# Main_Power.net
KiCad netlist of a schematic drawn in Altium Designer
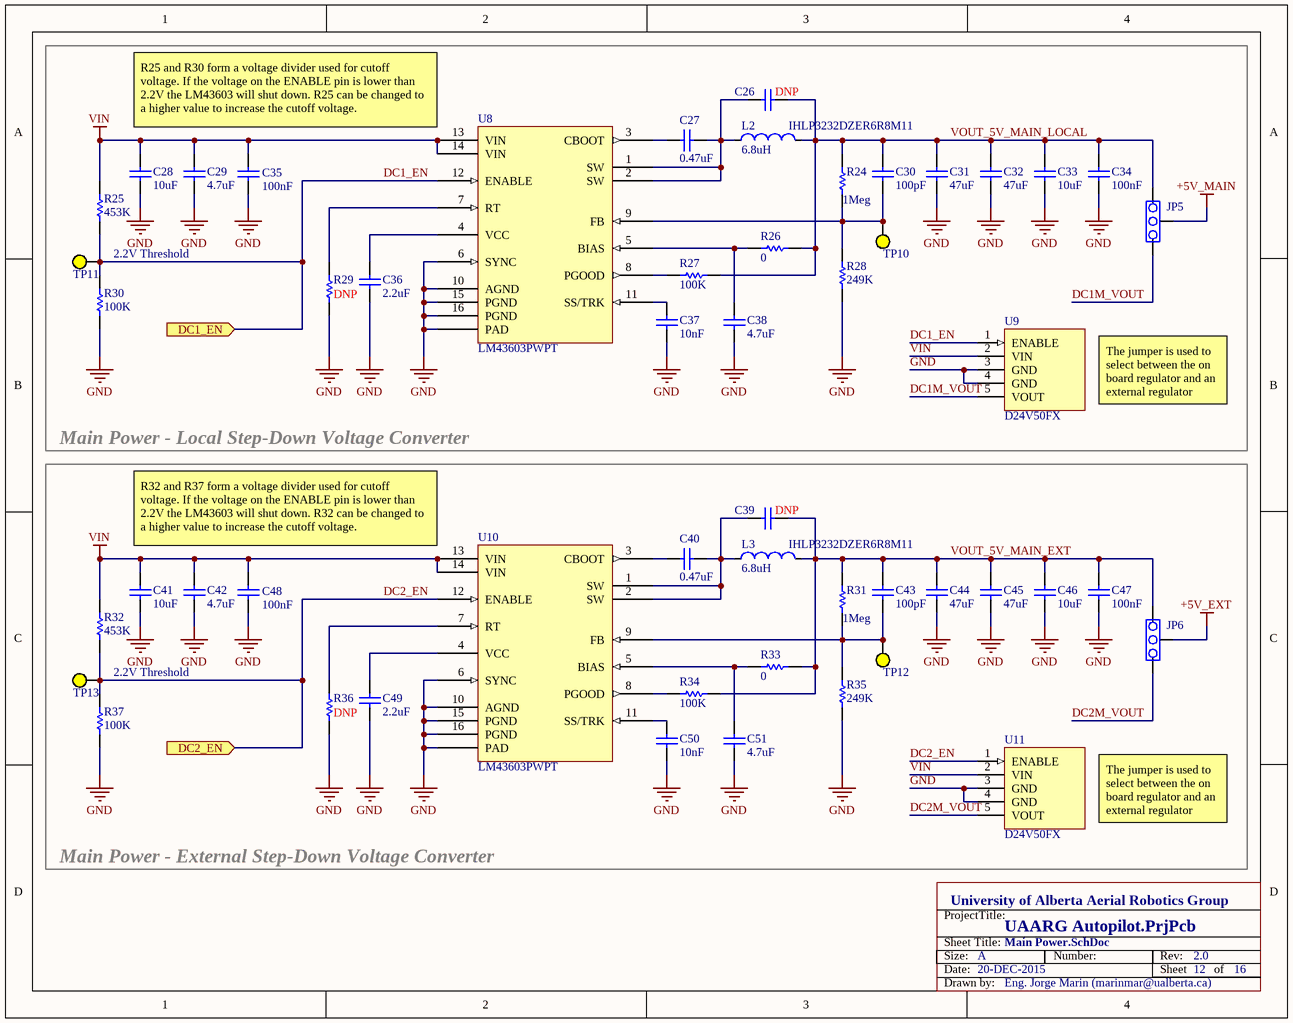
[diagram p0: Main Power.SchDoc]

(export (version "E")
  (design (tool "Eeschema 10.0.6"))
  (components
    (comp (ref "C26")
      (value "Cap")
      (footprint "CAP_0402[1005M]")
      (description "Capacitor")
      (fields (field (name "NOTE") "DNP"))
      (libsource (lib "UAARG Autopilot") (part "CAP"))
    )
    (comp (ref "C27")
      (value "0.47uF")
      (footprint "CAP_0402[1005M]")
      (description "CAP CER 0.1UF 10V 10% X7R 0402")
      (fields
        (field (name "MANUFACTURER PART NUMBER") "CC0402ZRY5V7BB474")
        (field (name "MANUFACTURER") "Yageo")
      )
      (libsource (lib "UAARG Autopilot") (part "CAP"))
    )
    (comp (ref "C28")
      (value "10uF")
      (footprint "UAARG Autopilot:CAP_1210[3225M]")
      (description "Capacitor")
      (fields
        (field (name "MANUFACTURER PART NUMBER") "CL32B106KBJNNNE")
        (field (name "MANUFACTURER") "Samsung Electro-Mechanics America, Inc.")
      )
      (libsource (lib "UAARG Autopilot") (part "CAP"))
    )
    (comp (ref "C29")
      (value "4.7uF")
      (footprint "UAARG Autopilot:CAP_1210[3225M]")
      (description "Capacitor")
      (fields
        (field (name "MANUFACTURER PART NUMBER") "CL32B475KBUYNNE")
        (field (name "MANUFACTURER") "Samsung Electro-Mechanics America, Inc.")
      )
      (libsource (lib "UAARG Autopilot") (part "CAP"))
    )
    (comp (ref "C30")
      (value "100pF")
      (footprint "CAP_0402[1005M]")
      (description "CAP CER 0.1UF 10V 10% X7R 0402")
      (fields
        (field (name "MANUFACTURER") "Yageo")
        (field (name "MANUFACTURER PART NUMBER") "CC0402JRNPO9BN101")
      )
      (libsource (lib "UAARG Autopilot") (part "CAP"))
    )
    (comp (ref "C31")
      (value "47uF")
      (footprint "UAARG Autopilot:CAP_1210[3225M]")
      (description "Capacitor")
      (fields
        (field (name "MANUFACTURER") "Murata Electronics North America")
        (field (name "MANUFACTURER PART NUMBER") "GRM32ER71A476KE15L")
      )
      (libsource (lib "UAARG Autopilot") (part "CAP"))
    )
    (comp (ref "C32")
      (value "47uF")
      (footprint "UAARG Autopilot:CAP_1210[3225M]")
      (description "Capacitor")
      (fields
        (field (name "MANUFACTURER") "Murata Electronics North America")
        (field (name "MANUFACTURER PART NUMBER") "GRM32ER71A476KE15L")
      )
      (libsource (lib "UAARG Autopilot") (part "CAP"))
    )
    (comp (ref "C33")
      (value "10uF")
      (footprint "UAARG Autopilot:CAP_0805[2012M]")
      (description "Capacitor")
      (fields
        (field (name "MANUFACTURER PART NUMBER") "CC0805KKX5R7BB106")
        (field (name "MANUFACTURER") "Yageo")
      )
      (libsource (lib "UAARG Autopilot") (part "CAP"))
    )
    (comp (ref "C34")
      (value "100nF")
      (footprint "UAARG Autopilot:CAP_0603[1608M]")
      (description "Capacitor")
      (fields
        (field (name "MANUFACTURER PART NUMBER") "CC0603KPX7R7BB104")
        (field (name "MANUFACTURER") "Yageo")
      )
      (libsource (lib "UAARG Autopilot") (part "CAP"))
    )
    (comp (ref "C35")
      (value "100nF")
      (footprint "CAP_0402[1005M]")
      (description "Capacitor")
      (fields
        (field (name "MANUFACTURER") "Yageo")
        (field (name "MANUFACTURER PART NUMBER") "CC0402KRX7R6BB104")
      )
      (libsource (lib "UAARG Autopilot") (part "CAP"))
    )
    (comp (ref "C36")
      (value "2.2uF")
      (footprint "CAP_0402[1005M]")
      (description "Capacitor")
      (fields
        (field (name "MANUFACTURER") "Yageo")
        (field (name "MANUFACTURER PART NUMBER") "CC0402MRX5R5BB225")
      )
      (libsource (lib "UAARG Autopilot") (part "CAP"))
    )
    (comp (ref "C37")
      (value "10nF")
      (footprint "CAP_0402[1005M]")
      (description "Capacitor")
      (fields
        (field (name "MANUFACTURER") "Yageo")
        (field (name "MANUFACTURER PART NUMBER") "CC0402KRX7R7BB103")
      )
      (libsource (lib "UAARG Autopilot") (part "CAP"))
    )
    (comp (ref "C38")
      (value "4.7uF")
      (footprint "CAP_0402[1005M]")
      (description "Capacitor")
      (fields
        (field (name "MANUFACTURER") "Yageo")
        (field (name "MANUFACTURER PART NUMBER") "CC0402MRX5R6BB475")
      )
      (libsource (lib "UAARG Autopilot") (part "CAP"))
    )
    (comp (ref "C39")
      (value "Cap")
      (footprint "CAP_0402[1005M]")
      (description "Capacitor")
      (fields (field (name "NOTE") "DNP"))
      (libsource (lib "UAARG Autopilot") (part "CAP"))
    )
    (comp (ref "C40")
      (value "0.47uF")
      (footprint "CAP_0402[1005M]")
      (description "CAP CER 0.1UF 10V 10% X7R 0402")
      (fields
        (field (name "MANUFACTURER PART NUMBER") "CC0402ZRY5V7BB474")
        (field (name "MANUFACTURER") "Yageo")
      )
      (libsource (lib "UAARG Autopilot") (part "CAP"))
    )
    (comp (ref "C41")
      (value "10uF")
      (footprint "UAARG Autopilot:CAP_1210[3225M]")
      (description "Capacitor")
      (fields
        (field (name "MANUFACTURER PART NUMBER") "CL32B106KBJNNNE")
        (field (name "MANUFACTURER") "Samsung Electro-Mechanics America, Inc.")
      )
      (libsource (lib "UAARG Autopilot") (part "CAP"))
    )
    (comp (ref "C42")
      (value "4.7uF")
      (footprint "UAARG Autopilot:CAP_1210[3225M]")
      (description "Capacitor")
      (fields
        (field (name "MANUFACTURER PART NUMBER") "CL32B475KBUYNNE")
        (field (name "MANUFACTURER") "Samsung Electro-Mechanics America, Inc.")
      )
      (libsource (lib "UAARG Autopilot") (part "CAP"))
    )
    (comp (ref "C43")
      (value "100pF")
      (footprint "CAP_0402[1005M]")
      (description "CAP CER 0.1UF 10V 10% X7R 0402")
      (fields
        (field (name "MANUFACTURER") "Yageo")
        (field (name "MANUFACTURER PART NUMBER") "CC0402JRNPO9BN101")
      )
      (libsource (lib "UAARG Autopilot") (part "CAP"))
    )
    (comp (ref "C44")
      (value "47uF")
      (footprint "UAARG Autopilot:CAP_1210[3225M]")
      (description "Capacitor")
      (fields
        (field (name "MANUFACTURER") "Murata Electronics North America")
        (field (name "MANUFACTURER PART NUMBER") "GRM32ER71A476KE15L")
      )
      (libsource (lib "UAARG Autopilot") (part "CAP"))
    )
    (comp (ref "C45")
      (value "47uF")
      (footprint "UAARG Autopilot:CAP_1210[3225M]")
      (description "Capacitor")
      (fields
        (field (name "MANUFACTURER") "Murata Electronics North America")
        (field (name "MANUFACTURER PART NUMBER") "GRM32ER71A476KE15L")
      )
      (libsource (lib "UAARG Autopilot") (part "CAP"))
    )
    (comp (ref "C46")
      (value "10uF")
      (footprint "UAARG Autopilot:CAP_0805[2012M]")
      (description "Capacitor")
      (fields
        (field (name "MANUFACTURER PART NUMBER") "CC0805KKX5R7BB106")
        (field (name "MANUFACTURER") "Yageo")
      )
      (libsource (lib "UAARG Autopilot") (part "CAP"))
    )
    (comp (ref "C47")
      (value "100nF")
      (footprint "UAARG Autopilot:CAP_0603[1608M]")
      (description "Capacitor")
      (fields
        (field (name "MANUFACTURER PART NUMBER") "CC0603KPX7R7BB104")
        (field (name "MANUFACTURER") "Yageo")
      )
      (libsource (lib "UAARG Autopilot") (part "CAP"))
    )
    (comp (ref "C48")
      (value "100nF")
      (footprint "CAP_0402[1005M]")
      (description "Capacitor")
      (fields
        (field (name "MANUFACTURER") "Yageo")
        (field (name "MANUFACTURER PART NUMBER") "CC0402KRX7R6BB104")
      )
      (libsource (lib "UAARG Autopilot") (part "CAP"))
    )
    (comp (ref "C49")
      (value "2.2uF")
      (footprint "CAP_0402[1005M]")
      (description "Capacitor")
      (fields
        (field (name "MANUFACTURER") "Yageo")
        (field (name "MANUFACTURER PART NUMBER") "CC0402MRX5R5BB225")
      )
      (libsource (lib "UAARG Autopilot") (part "CAP"))
    )
    (comp (ref "C50")
      (value "10nF")
      (footprint "CAP_0402[1005M]")
      (description "Capacitor")
      (fields
        (field (name "MANUFACTURER") "Yageo")
        (field (name "MANUFACTURER PART NUMBER") "CC0402KRX7R7BB103")
      )
      (libsource (lib "UAARG Autopilot") (part "CAP"))
    )
    (comp (ref "C51")
      (value "4.7uF")
      (footprint "CAP_0402[1005M]")
      (description "Capacitor")
      (fields
        (field (name "MANUFACTURER") "Yageo")
        (field (name "MANUFACTURER PART NUMBER") "CC0402MRX5R6BB475")
      )
      (libsource (lib "UAARG Autopilot") (part "CAP"))
    )
    (comp (ref "JP5")
      (value "Jumper")
      (footprint "JUMPER_3POS")
      (libsource (lib "UAARG Autopilot") (part "Jumper_2"))
    )
    (comp (ref "JP6")
      (value "Jumper")
      (footprint "JUMPER_3POS")
      (libsource (lib "UAARG Autopilot") (part "Jumper_2"))
    )
    (comp (ref "L2")
      (value "6.8uH")
      (footprint "IHLP-3232DZ")
      (description "FIXED IND 6.8UH 7A 33.4 MOHM SMD")
      (fields
        (field (name "MANUFACTURER") "Vishay Dale")
        (field (name "MANUFACTURER PART NUMBER") "IHLP3232DZER6R8M11")
      )
      (libsource (lib "UAARG Autopilot") (part "Inductor"))
    )
    (comp (ref "L3")
      (value "6.8uH")
      (footprint "IHLP-3232DZ")
      (description "FIXED IND 6.8UH 7A 33.4 MOHM SMD")
      (fields
        (field (name "MANUFACTURER") "Vishay Dale")
        (field (name "MANUFACTURER PART NUMBER") "IHLP3232DZER6R8M11")
      )
      (libsource (lib "UAARG Autopilot") (part "Inductor"))
    )
    (comp (ref "R24")
      (value "1Meg")
      (footprint "RES_0402[1005M]")
      (description "Resistor")
      (fields
        (field (name "MANUFACTURER") "Rohm Semiconductor")
        (field (name "MANUFACTURER PART NUMBER") "MCR01MRTF1004")
      )
      (libsource (lib "UAARG Autopilot") (part "RES"))
    )
    (comp (ref "R25")
      (value "453K")
      (footprint "RES_0603[1608M]")
      (description "Resistor")
      (fields
        (field (name "MANUFACTURER") "Yageo")
        (field (name "MANUFACTURER PART NUMBER") "RC0603FR-07453KL")
      )
      (libsource (lib "UAARG Autopilot") (part "RES"))
    )
    (comp (ref "R26")
      (value "0")
      (footprint "JUMPER_RES_0402")
      (description "Resistor")
      (fields
        (field (name "MANUFACTURER PART NUMBER") "RC0402JR-070RL")
        (field (name "MANUFACTURER") "Yageo")
      )
      (libsource (lib "UAARG Autopilot") (part "RES"))
    )
    (comp (ref "R27")
      (value "100K")
      (footprint "RES_0402[1005M]")
      (description "Resistor")
      (fields
        (field (name "MANUFACTURER") "Yageo")
        (field (name "MANUFACTURER PART NUMBER") "RC0402FR-07100KL")
      )
      (libsource (lib "UAARG Autopilot") (part "RES"))
    )
    (comp (ref "R28")
      (value "249K")
      (footprint "RES_0402[1005M]")
      (description "Resistor")
      (fields
        (field (name "MANUFACTURER") "Rohm Semiconductor")
        (field (name "MANUFACTURER PART NUMBER") "MCR01MRTF2493")
      )
      (libsource (lib "UAARG Autopilot") (part "RES"))
    )
    (comp (ref "R29")
      (value "RES")
      (footprint "RES_0402[1005M]")
      (description "Resistor")
      (fields (field (name "NOTE") "DNP"))
      (libsource (lib "UAARG Autopilot") (part "RES"))
    )
    (comp (ref "R30")
      (value "100K")
      (footprint "RES_0603[1608M]")
      (description "Resistor")
      (fields
        (field (name "MANUFACTURER") "Yageo")
        (field (name "MANUFACTURER PART NUMBER") "RC0603FR-07100KL")
      )
      (libsource (lib "UAARG Autopilot") (part "RES"))
    )
    (comp (ref "R31")
      (value "1Meg")
      (footprint "RES_0402[1005M]")
      (description "Resistor")
      (fields
        (field (name "MANUFACTURER") "Rohm Semiconductor")
        (field (name "MANUFACTURER PART NUMBER") "MCR01MRTF1004")
      )
      (libsource (lib "UAARG Autopilot") (part "RES"))
    )
    (comp (ref "R32")
      (value "453K")
      (footprint "RES_0603[1608M]")
      (description "Resistor")
      (fields
        (field (name "MANUFACTURER") "Yageo")
        (field (name "MANUFACTURER PART NUMBER") "RC0603FR-07453KL")
      )
      (libsource (lib "UAARG Autopilot") (part "RES"))
    )
    (comp (ref "R33")
      (value "0")
      (footprint "JUMPER_RES_0402")
      (description "Resistor")
      (fields
        (field (name "MANUFACTURER PART NUMBER") "RC0402JR-070RL")
        (field (name "MANUFACTURER") "Yageo")
      )
      (libsource (lib "UAARG Autopilot") (part "RES"))
    )
    (comp (ref "R34")
      (value "100K")
      (footprint "RES_0402[1005M]")
      (description "Resistor")
      (fields
        (field (name "MANUFACTURER") "Yageo")
        (field (name "MANUFACTURER PART NUMBER") "RC0402FR-07100KL")
      )
      (libsource (lib "UAARG Autopilot") (part "RES"))
    )
    (comp (ref "R35")
      (value "249K")
      (footprint "RES_0402[1005M]")
      (description "Resistor")
      (fields
        (field (name "MANUFACTURER") "Rohm Semiconductor")
        (field (name "MANUFACTURER PART NUMBER") "MCR01MRTF2493")
      )
      (libsource (lib "UAARG Autopilot") (part "RES"))
    )
    (comp (ref "R36")
      (value "RES")
      (footprint "RES_0402[1005M]")
      (description "Resistor")
      (fields (field (name "NOTE") "DNP"))
      (libsource (lib "UAARG Autopilot") (part "RES"))
    )
    (comp (ref "R37")
      (value "100K")
      (footprint "RES_0603[1608M]")
      (description "Resistor")
      (fields
        (field (name "MANUFACTURER") "Yageo")
        (field (name "MANUFACTURER PART NUMBER") "RC0603FR-07100KL")
      )
      (libsource (lib "UAARG Autopilot") (part "RES"))
    )
    (comp (ref "TP10")
      (value "Test Point SIG")
      (footprint "TP_SMD_1_SILK")
      (description "Test Point Signal")
      (libsource (lib "UAARG Autopilot") (part "Test Point SIG"))
    )
    (comp (ref "TP11")
      (value "Test Point SIG")
      (footprint "TP_TH_1_SILK")
      (description "Test Point Signal")
      (libsource (lib "UAARG Autopilot") (part "Test Point SIG"))
    )
    (comp (ref "TP12")
      (value "Test Point SIG")
      (footprint "TP_SMD_1_SILK")
      (description "Test Point Signal")
      (libsource (lib "UAARG Autopilot") (part "Test Point SIG"))
    )
    (comp (ref "TP13")
      (value "Test Point SIG")
      (footprint "TP_TH_1_SILK")
      (description "Test Point Signal")
      (libsource (lib "UAARG Autopilot") (part "Test Point SIG"))
    )
    (comp (ref "U8")
      (value "LM43603PWPT")
      (footprint "HTSSOP-16")
      (description "Simple Switcher 3.5V to 36V 3A Synchronous Step-Down Voltage Converter")
      (fields (field (name "MANUFACTURER") "Texas Instruments"))
      (libsource (lib "UAARG Autopilot") (part "LM43603PWPT"))
    )
    (comp (ref "U9")
      (value "D24V__F_")
      (footprint "D24V__F_")
      (description "Pololu Buck Converter D24V__F_ series")
      (fields (field (name "MANUFACTURER") "Pololu") (field (name "MANUFACTURER PART NUMBER") "D24V50FX"))
      (libsource (lib "UAARG Autopilot") (part "D24V__F_"))
    )
    (comp (ref "U10")
      (value "LM43603PWPT")
      (footprint "HTSSOP-16")
      (description "Simple Switcher 3.5V to 36V 3A Synchronous Step-Down Voltage Converter")
      (fields (field (name "MANUFACTURER") "Texas Instruments"))
      (libsource (lib "UAARG Autopilot") (part "LM43603PWPT"))
    )
    (comp (ref "U11")
      (value "D24V__F_")
      (footprint "D24V__F_")
      (description "Pololu Buck Converter D24V__F_ series")
      (fields (field (name "MANUFACTURER") "Pololu") (field (name "MANUFACTURER PART NUMBER") "D24V50FX"))
      (libsource (lib "UAARG Autopilot") (part "D24V__F_"))
    )
  )
  (nets
    (net (code "1") (name "+5V_EXT") (class "Default")
      (node (ref "JP6") (pin "2") (pinfunction "2_2") (pintype "passive"))
    )
    (net (code "2") (name "+5V_MAIN") (class "Default")
      (node (ref "JP5") (pin "2") (pinfunction "2_2") (pintype "passive"))
    )
    (net (code "3") (name "/DC1M_VOUT") (class "Default")
      (node (ref "JP5") (pin "3") (pinfunction "3_3") (pintype "passive"))
      (node (ref "U9") (pin "5") (pinfunction "VOUT_5") (pintype "power_in"))
    )
    (net (code "4") (name "/DC1_EN") (class "Default")
      (node (ref "R25") (pin "1") (pinfunction "1_1") (pintype "passive"))
      (node (ref "R30") (pin "2") (pinfunction "2_2") (pintype "passive"))
      (node (ref "TP11") (pin "1") (pinfunction "1_1") (pintype "passive"))
      (node (ref "U8") (pin "12") (pinfunction "ENABLE_12") (pintype "input"))
      (node (ref "U9") (pin "1") (pinfunction "ENABLE_1") (pintype "input"))
    )
    (net (code "5") (name "/DC2M_VOUT") (class "Default")
      (node (ref "JP6") (pin "3") (pinfunction "3_3") (pintype "passive"))
      (node (ref "U11") (pin "5") (pinfunction "VOUT_5") (pintype "power_in"))
    )
    (net (code "6") (name "/DC2_EN") (class "Default")
      (node (ref "R32") (pin "1") (pinfunction "1_1") (pintype "passive"))
      (node (ref "R37") (pin "2") (pinfunction "2_2") (pintype "passive"))
      (node (ref "TP13") (pin "1") (pinfunction "1_1") (pintype "passive"))
      (node (ref "U10") (pin "12") (pinfunction "ENABLE_12") (pintype "input"))
      (node (ref "U11") (pin "1") (pinfunction "ENABLE_1") (pintype "input"))
    )
    (net (code "7") (name "/VOUT_5V_MAIN_EXT") (class "Default")
      (node (ref "C39") (pin "2") (pinfunction "2_2") (pintype "passive"))
      (node (ref "C43") (pin "1") (pinfunction "1_1") (pintype "passive"))
      (node (ref "C44") (pin "1") (pinfunction "1_1") (pintype "passive"))
      (node (ref "C45") (pin "1") (pinfunction "1_1") (pintype "passive"))
      (node (ref "C46") (pin "1") (pinfunction "1_1") (pintype "passive"))
      (node (ref "C47") (pin "1") (pinfunction "1_1") (pintype "passive"))
      (node (ref "JP6") (pin "1") (pinfunction "1_1") (pintype "passive"))
      (node (ref "L3") (pin "2") (pinfunction "2_2") (pintype "passive"))
      (node (ref "R31") (pin "1") (pinfunction "1_1") (pintype "passive"))
      (node (ref "R33") (pin "1") (pinfunction "1_1") (pintype "passive"))
      (node (ref "R34") (pin "1") (pinfunction "1_1") (pintype "passive"))
    )
    (net (code "8") (name "/VOUT_5V_MAIN_LOCAL") (class "Default")
      (node (ref "C26") (pin "2") (pinfunction "2_2") (pintype "passive"))
      (node (ref "C30") (pin "1") (pinfunction "1_1") (pintype "passive"))
      (node (ref "C31") (pin "1") (pinfunction "1_1") (pintype "passive"))
      (node (ref "C32") (pin "1") (pinfunction "1_1") (pintype "passive"))
      (node (ref "C33") (pin "1") (pinfunction "1_1") (pintype "passive"))
      (node (ref "C34") (pin "1") (pinfunction "1_1") (pintype "passive"))
      (node (ref "JP5") (pin "1") (pinfunction "1_1") (pintype "passive"))
      (node (ref "L2") (pin "2") (pinfunction "2_2") (pintype "passive"))
      (node (ref "R24") (pin "1") (pinfunction "1_1") (pintype "passive"))
      (node (ref "R26") (pin "1") (pinfunction "1_1") (pintype "passive"))
      (node (ref "R27") (pin "1") (pinfunction "1_1") (pintype "passive"))
    )
    (net (code "9") (name "GND") (class "Default")
      (node (ref "C28") (pin "2") (pinfunction "2_2") (pintype "passive"))
      (node (ref "C29") (pin "2") (pinfunction "2_2") (pintype "passive"))
      (node (ref "C31") (pin "2") (pinfunction "2_2") (pintype "passive"))
      (node (ref "C32") (pin "2") (pinfunction "2_2") (pintype "passive"))
      (node (ref "C33") (pin "2") (pinfunction "2_2") (pintype "passive"))
      (node (ref "C34") (pin "2") (pinfunction "2_2") (pintype "passive"))
      (node (ref "C35") (pin "2") (pinfunction "2_2") (pintype "passive"))
      (node (ref "C36") (pin "1") (pinfunction "1_1") (pintype "passive"))
      (node (ref "C37") (pin "2") (pinfunction "2_2") (pintype "passive"))
      (node (ref "C38") (pin "2") (pinfunction "2_2") (pintype "passive"))
      (node (ref "C41") (pin "2") (pinfunction "2_2") (pintype "passive"))
      (node (ref "C42") (pin "2") (pinfunction "2_2") (pintype "passive"))
      (node (ref "C44") (pin "2") (pinfunction "2_2") (pintype "passive"))
      (node (ref "C45") (pin "2") (pinfunction "2_2") (pintype "passive"))
      (node (ref "C46") (pin "2") (pinfunction "2_2") (pintype "passive"))
      (node (ref "C47") (pin "2") (pinfunction "2_2") (pintype "passive"))
      (node (ref "C48") (pin "2") (pinfunction "2_2") (pintype "passive"))
      (node (ref "C49") (pin "1") (pinfunction "1_1") (pintype "passive"))
      (node (ref "C50") (pin "2") (pinfunction "2_2") (pintype "passive"))
      (node (ref "C51") (pin "2") (pinfunction "2_2") (pintype "passive"))
      (node (ref "R28") (pin "2") (pinfunction "2_2") (pintype "passive"))
      (node (ref "R29") (pin "1") (pinfunction "1_1") (pintype "passive"))
      (node (ref "R30") (pin "1") (pinfunction "1_1") (pintype "passive"))
      (node (ref "R35") (pin "2") (pinfunction "2_2") (pintype "passive"))
      (node (ref "R36") (pin "1") (pinfunction "1_1") (pintype "passive"))
      (node (ref "R37") (pin "1") (pinfunction "1_1") (pintype "passive"))
      (node (ref "U10") (pin "10") (pinfunction "AGND_10") (pintype "power_in"))
      (node (ref "U10") (pin "15") (pinfunction "PGND_15") (pintype "power_in"))
      (node (ref "U10") (pin "16") (pinfunction "PGND_16") (pintype "power_in"))
      (node (ref "U10") (pin "6") (pinfunction "SYNC_6") (pintype "input"))
      (node (ref "U10") (pin "EP") (pinfunction "PAD_EP") (pintype "power_in"))
      (node (ref "U11") (pin "3") (pinfunction "GND_3") (pintype "power_in"))
      (node (ref "U11") (pin "4") (pinfunction "GND_4") (pintype "power_in"))
      (node (ref "U8") (pin "10") (pinfunction "AGND_10") (pintype "power_in"))
      (node (ref "U8") (pin "15") (pinfunction "PGND_15") (pintype "power_in"))
      (node (ref "U8") (pin "16") (pinfunction "PGND_16") (pintype "power_in"))
      (node (ref "U8") (pin "6") (pinfunction "SYNC_6") (pintype "input"))
      (node (ref "U8") (pin "EP") (pinfunction "PAD_EP") (pintype "power_in"))
      (node (ref "U9") (pin "3") (pinfunction "GND_3") (pintype "power_in"))
      (node (ref "U9") (pin "4") (pinfunction "GND_4") (pintype "power_in"))
    )
    (net (code "10") (name "Net-(C26-Pad1)") (class "Default")
      (node (ref "C26") (pin "1") (pinfunction "1_1") (pintype "passive"))
      (node (ref "C27") (pin "2") (pinfunction "2_2") (pintype "passive"))
      (node (ref "L2") (pin "1") (pinfunction "1_1") (pintype "passive"))
      (node (ref "U8") (pin "1") (pinfunction "SW_1") (pintype "power_in"))
      (node (ref "U8") (pin "2") (pinfunction "SW_2") (pintype "power_in"))
    )
    (net (code "11") (name "Net-(C39-Pad1)") (class "Default")
      (node (ref "C39") (pin "1") (pinfunction "1_1") (pintype "passive"))
      (node (ref "C40") (pin "2") (pinfunction "2_2") (pintype "passive"))
      (node (ref "L3") (pin "1") (pinfunction "1_1") (pintype "passive"))
      (node (ref "U10") (pin "1") (pinfunction "SW_1") (pintype "power_in"))
      (node (ref "U10") (pin "2") (pinfunction "SW_2") (pintype "power_in"))
    )
    (net (code "12") (name "Net-(U8-BIAS)") (class "Default")
      (node (ref "C38") (pin "1") (pinfunction "1_1") (pintype "passive"))
      (node (ref "R26") (pin "2") (pinfunction "2_2") (pintype "passive"))
      (node (ref "U8") (pin "5") (pinfunction "BIAS_5") (pintype "input"))
    )
    (net (code "13") (name "Net-(U8-CBOOT)") (class "Default")
      (node (ref "C27") (pin "1") (pinfunction "1_1") (pintype "passive"))
      (node (ref "U8") (pin "3") (pinfunction "CBOOT_3") (pintype "output"))
    )
    (net (code "14") (name "Net-(U8-FB)") (class "Default")
      (node (ref "C30") (pin "2") (pinfunction "2_2") (pintype "passive"))
      (node (ref "R24") (pin "2") (pinfunction "2_2") (pintype "passive"))
      (node (ref "R28") (pin "1") (pinfunction "1_1") (pintype "passive"))
      (node (ref "TP10") (pin "1") (pinfunction "1_1") (pintype "passive"))
      (node (ref "U8") (pin "9") (pinfunction "FB_9") (pintype "input"))
    )
    (net (code "15") (name "Net-(U8-PGOOD)") (class "Default")
      (node (ref "R27") (pin "2") (pinfunction "2_2") (pintype "passive"))
      (node (ref "U8") (pin "8") (pinfunction "PGOOD_8") (pintype "output"))
    )
    (net (code "16") (name "Net-(U8-RT)") (class "Default")
      (node (ref "R29") (pin "2") (pinfunction "2_2") (pintype "passive"))
      (node (ref "U8") (pin "7") (pinfunction "RT_7") (pintype "input"))
    )
    (net (code "17") (name "Net-(U8-SS{slash}TRK)") (class "Default")
      (node (ref "C37") (pin "1") (pinfunction "1_1") (pintype "passive"))
      (node (ref "U8") (pin "11") (pinfunction "SS/TRK_11") (pintype "input"))
    )
    (net (code "18") (name "Net-(U8-VCC)") (class "Default")
      (node (ref "C36") (pin "2") (pinfunction "2_2") (pintype "passive"))
      (node (ref "U8") (pin "4") (pinfunction "VCC_4") (pintype "power_in"))
    )
    (net (code "19") (name "Net-(U10-BIAS)") (class "Default")
      (node (ref "C51") (pin "1") (pinfunction "1_1") (pintype "passive"))
      (node (ref "R33") (pin "2") (pinfunction "2_2") (pintype "passive"))
      (node (ref "U10") (pin "5") (pinfunction "BIAS_5") (pintype "input"))
    )
    (net (code "20") (name "Net-(U10-CBOOT)") (class "Default")
      (node (ref "C40") (pin "1") (pinfunction "1_1") (pintype "passive"))
      (node (ref "U10") (pin "3") (pinfunction "CBOOT_3") (pintype "output"))
    )
    (net (code "21") (name "Net-(U10-FB)") (class "Default")
      (node (ref "C43") (pin "2") (pinfunction "2_2") (pintype "passive"))
      (node (ref "R31") (pin "2") (pinfunction "2_2") (pintype "passive"))
      (node (ref "R35") (pin "1") (pinfunction "1_1") (pintype "passive"))
      (node (ref "TP12") (pin "1") (pinfunction "1_1") (pintype "passive"))
      (node (ref "U10") (pin "9") (pinfunction "FB_9") (pintype "input"))
    )
    (net (code "22") (name "Net-(U10-PGOOD)") (class "Default")
      (node (ref "R34") (pin "2") (pinfunction "2_2") (pintype "passive"))
      (node (ref "U10") (pin "8") (pinfunction "PGOOD_8") (pintype "output"))
    )
    (net (code "23") (name "Net-(U10-RT)") (class "Default")
      (node (ref "R36") (pin "2") (pinfunction "2_2") (pintype "passive"))
      (node (ref "U10") (pin "7") (pinfunction "RT_7") (pintype "input"))
    )
    (net (code "24") (name "Net-(U10-SS{slash}TRK)") (class "Default")
      (node (ref "C50") (pin "1") (pinfunction "1_1") (pintype "passive"))
      (node (ref "U10") (pin "11") (pinfunction "SS/TRK_11") (pintype "input"))
    )
    (net (code "25") (name "Net-(U10-VCC)") (class "Default")
      (node (ref "C49") (pin "2") (pinfunction "2_2") (pintype "passive"))
      (node (ref "U10") (pin "4") (pinfunction "VCC_4") (pintype "power_in"))
    )
    (net (code "26") (name "VIN") (class "Default")
      (node (ref "C28") (pin "1") (pinfunction "1_1") (pintype "passive"))
      (node (ref "C29") (pin "1") (pinfunction "1_1") (pintype "passive"))
      (node (ref "C35") (pin "1") (pinfunction "1_1") (pintype "passive"))
      (node (ref "C41") (pin "1") (pinfunction "1_1") (pintype "passive"))
      (node (ref "C42") (pin "1") (pinfunction "1_1") (pintype "passive"))
      (node (ref "C48") (pin "1") (pinfunction "1_1") (pintype "passive"))
      (node (ref "R25") (pin "2") (pinfunction "2_2") (pintype "passive"))
      (node (ref "R32") (pin "2") (pinfunction "2_2") (pintype "passive"))
      (node (ref "U10") (pin "13") (pinfunction "VIN_13") (pintype "power_in"))
      (node (ref "U10") (pin "14") (pinfunction "VIN_14") (pintype "power_in"))
      (node (ref "U11") (pin "2") (pinfunction "VIN_2") (pintype "power_in"))
      (node (ref "U8") (pin "13") (pinfunction "VIN_13") (pintype "power_in"))
      (node (ref "U8") (pin "14") (pinfunction "VIN_14") (pintype "power_in"))
      (node (ref "U9") (pin "2") (pinfunction "VIN_2") (pintype "power_in"))
    )
  )
)
